# 2_main_mcu.net
KiCad netlist of a schematic drawn in Altium Designer
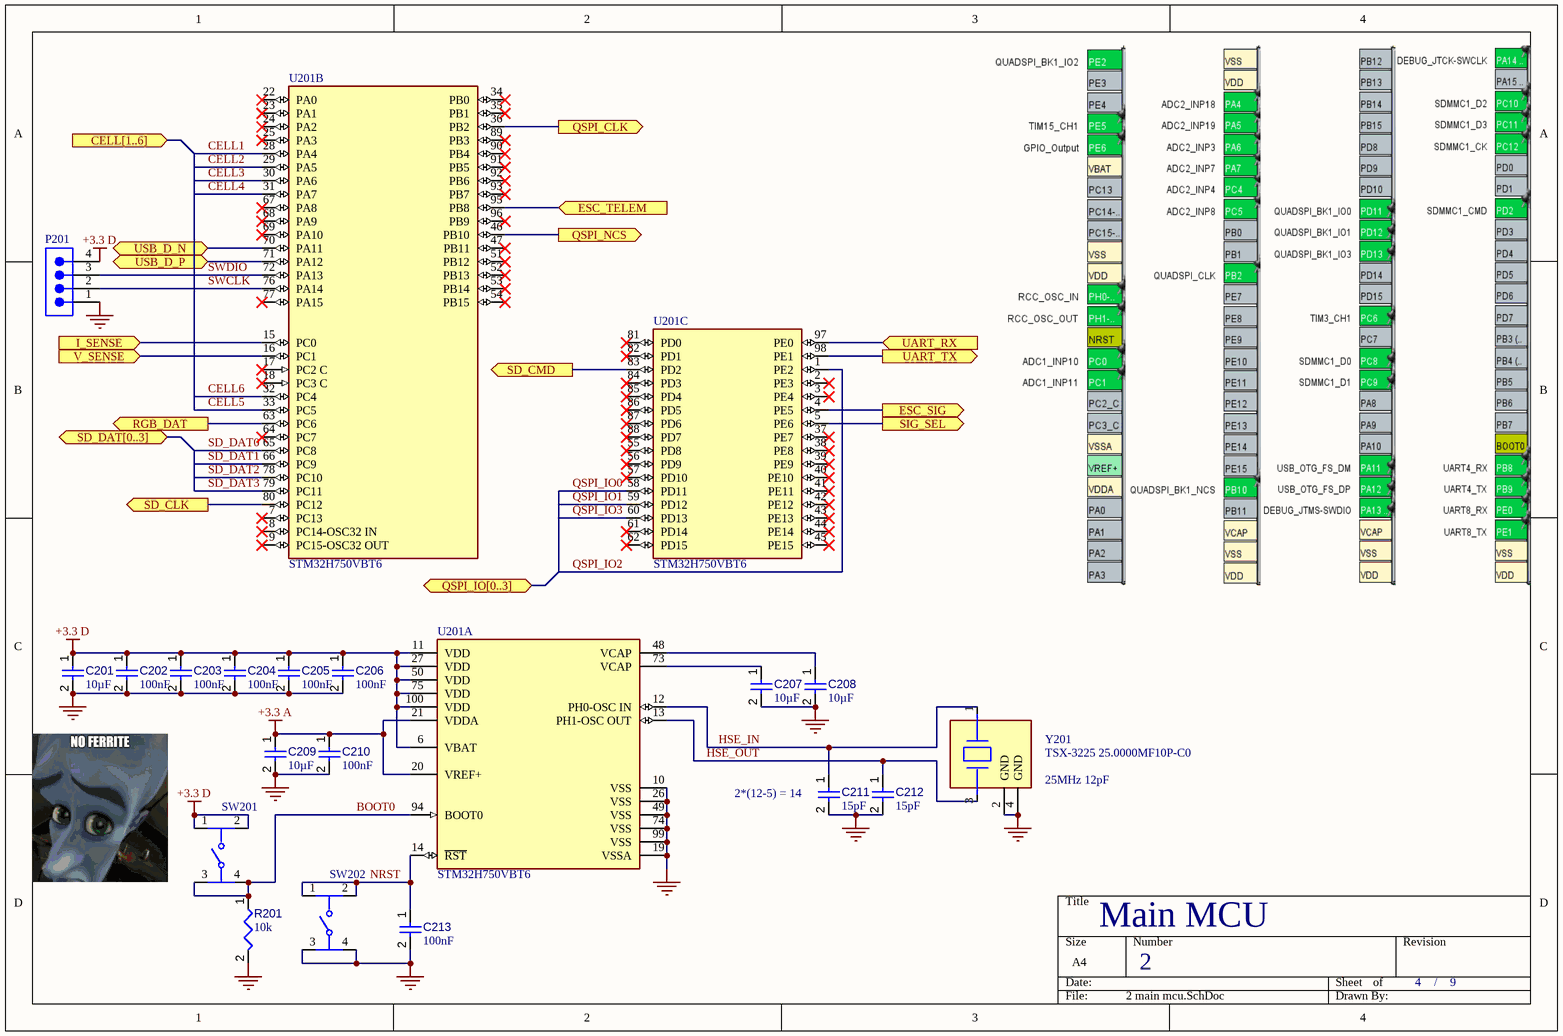
[diagram p0: 2 main mcu.SchDoc]

(export (version "E")
  (design (tool "Eeschema 10.0.6"))
  (components
    (comp (ref "C201")
      (value "10µF")
      (footprint "CAPC0603(1608)100_L")
      (description "Chip Capacitor, 10µF +/-20%, 10V, 0603, Thickness 1 mm")
      (fields (field (name "TOLERANCE") "10%") (field (name "Comment") "Capacitor 10µF +/-20% 10V 0603"))
      (libsource (lib "UBC Uncrewed Aircraft Systems") (part "CAP-NP-2"))
    )
    (comp (ref "C202")
      (value "100nF")
      (footprint "CAPC0402(1005)60_L")
      (description "Chip Capacitor, 100nF +/-20%, 25V, 0402, Thickness 0.6 mm")
      (fields (field (name "TOLERANCE") "10%") (field (name "Comment") "Capacitor 100nF +/-20% 25V 0402"))
      (libsource (lib "UBC Uncrewed Aircraft Systems") (part "CAP-NP-2"))
    )
    (comp (ref "C203")
      (value "100nF")
      (footprint "CAPC0402(1005)60_L")
      (description "Chip Capacitor, 100nF +/-20%, 25V, 0402, Thickness 0.6 mm")
      (fields (field (name "TOLERANCE") "10%") (field (name "Comment") "Capacitor 100nF +/-20% 25V 0402"))
      (libsource (lib "UBC Uncrewed Aircraft Systems") (part "CAP-NP-2"))
    )
    (comp (ref "C204")
      (value "100nF")
      (footprint "CAPC0402(1005)60_L")
      (description "Chip Capacitor, 100nF +/-20%, 25V, 0402, Thickness 0.6 mm")
      (fields (field (name "TOLERANCE") "10%") (field (name "Comment") "Capacitor 100nF +/-20% 25V 0402"))
      (libsource (lib "UBC Uncrewed Aircraft Systems") (part "CAP-NP-2"))
    )
    (comp (ref "C205")
      (value "100nF")
      (footprint "CAPC0402(1005)60_L")
      (description "Chip Capacitor, 100nF +/-20%, 25V, 0402, Thickness 0.6 mm")
      (fields (field (name "TOLERANCE") "10%") (field (name "Comment") "Capacitor 100nF +/-20% 25V 0402"))
      (libsource (lib "UBC Uncrewed Aircraft Systems") (part "CAP-NP-2"))
    )
    (comp (ref "C206")
      (value "100nF")
      (footprint "CAPC0402(1005)60_L")
      (description "Chip Capacitor, 100nF +/-20%, 25V, 0402, Thickness 0.6 mm")
      (fields (field (name "TOLERANCE") "10%") (field (name "Comment") "Capacitor 100nF +/-20% 25V 0402"))
      (libsource (lib "UBC Uncrewed Aircraft Systems") (part "CAP-NP-2"))
    )
    (comp (ref "C207")
      (value "10µF")
      (footprint "CAPC0603(1608)100_L")
      (description "Chip Capacitor, 10µF +/-20%, 10V, 0603, Thickness 1 mm")
      (fields (field (name "TOLERANCE") "10%") (field (name "Comment") "Capacitor 10µF +/-20% 10V 0603"))
      (libsource (lib "UBC Uncrewed Aircraft Systems") (part "CAP-NP-2"))
    )
    (comp (ref "C208")
      (value "10µF")
      (footprint "CAPC0603(1608)100_L")
      (description "Chip Capacitor, 10µF +/-20%, 10V, 0603, Thickness 1 mm")
      (fields (field (name "TOLERANCE") "10%") (field (name "Comment") "Capacitor 10µF +/-20% 10V 0603"))
      (libsource (lib "UBC Uncrewed Aircraft Systems") (part "CAP-NP-2"))
    )
    (comp (ref "C209")
      (value "10µF")
      (footprint "CAPC0603(1608)100_L")
      (description "Chip Capacitor, 10µF +/-20%, 10V, 0603, Thickness 1 mm")
      (fields (field (name "TOLERANCE") "10%") (field (name "Comment") "Capacitor 10µF +/-20% 10V 0603"))
      (libsource (lib "UBC Uncrewed Aircraft Systems") (part "CAP-NP-2"))
    )
    (comp (ref "C210")
      (value "100nF")
      (footprint "CAPC0402(1005)60_L")
      (description "Chip Capacitor, 100nF +/-20%, 25V, 0402, Thickness 0.6 mm")
      (fields (field (name "TOLERANCE") "10%") (field (name "Comment") "Capacitor 100nF +/-20% 25V 0402"))
      (libsource (lib "UBC Uncrewed Aircraft Systems") (part "CAP-NP-2"))
    )
    (comp (ref "C211")
      (value "15pF")
      (footprint "CAPC0402(1005)60_L")
      (description "Chip Capacitor, 15pF +/-20%, 50V, 0402, Thickness 0.6 mm")
      (fields (field (name "TOLERANCE") "5%") (field (name "JLCPCB PART #") "C1548"))
      (libsource (lib "UBC Uncrewed Aircraft Systems") (part "CAP-NP-2"))
    )
    (comp (ref "C212")
      (value "15pF")
      (footprint "CAPC0402(1005)60_L")
      (description "Chip Capacitor, 15pF +/-20%, 50V, 0402, Thickness 0.6 mm")
      (fields (field (name "TOLERANCE") "5%") (field (name "JLCPCB PART #") "C1548"))
      (libsource (lib "UBC Uncrewed Aircraft Systems") (part "CAP-NP-2"))
    )
    (comp (ref "C213")
      (value "100nF")
      (footprint "CAPC0402(1005)60_L")
      (description "Chip Capacitor, 100nF +/-20%, 25V, 0402, Thickness 0.6 mm")
      (fields (field (name "TOLERANCE") "10%") (field (name "Comment") "Capacitor 100nF +/-20% 25V 0402"))
      (libsource (lib "UBC Uncrewed Aircraft Systems") (part "CAP-NP-2"))
    )
    (comp (ref "P201")
      (value "61300411121")
      (footprint "61300411121")
      (libsource (lib "Altium Content Vault") (part "Header_Male_1R_04P"))
    )
    (comp (ref "R201")
      (value "10k")
      (footprint "RESC0402(1005)_L")
      (description "Chip Resistor, 10 kOhms, +/-1 %, 63 mW, -55 to 125 degC, 0402")
      (fields (field (name "POWER") "63mW") (field (name "TOLERANCE") "1%"))
      (libsource (lib "UBC Uncrewed Aircraft Systems") (part "RES-2"))
    )
    (comp (ref "SW201")
      (value "PTS810SJM250SMTRLFS")
      (footprint "FP-PTS810SJM250SMTRLFS-MFG")
      (description "SWITCH TACTILE SPST-NO 0.05A 16V")
      (libsource (lib "Altium Content Vault") (part "1adf0dd01260c80cf25a44bfd6b99ba"))
    )
    (comp (ref "SW202")
      (value "PTS810SJM250SMTRLFS")
      (footprint "FP-PTS810SJM250SMTRLFS-MFG")
      (description "SWITCH TACTILE SPST-NO 0.05A 16V")
      (libsource (lib "Altium Content Vault") (part "1adf0dd01260c80cf25a44bfd6b99ba"))
    )
    (comp (ref "U201")
      (value "STM32H750VBT6")
      (footprint "FP-LQFP100-1L-MFG")
      (description "IC MCU 32BIT 128KB FLASH 100LQFP")
      (fields
        (field (name "OCTOPART") "https://octopart.com/stm32h750vbt6-stmicroelectronics-94048547")
        (field (name "MANUFACTURER") "STMicroelectronics")
      )
      (libsource (lib "Altium Content Vault") (part "aca449acb2b80670ba40d015d68dc7a"))
    )
    (comp (ref "Y201")
      (value "TSX-3225 25.0000MF10P-C0")
      (footprint "FP-TSX-3225-MFG")
      (description "CRYSTAL 25.0000MHZ 18PF SMD")
      (libsource (lib "Altium Content Vault") (part "927a1cf76fcef45674bd853ccf050d4"))
    )
  )
  (nets
    (net (code "1") (name "+3.3 A") (class "Default")
      (node (ref "C209") (pin "1") (pinfunction "1_1") (pintype "passive"))
      (node (ref "C210") (pin "1") (pinfunction "1_1") (pintype "passive"))
      (node (ref "U201") (pin "20") (pinfunction "VREF+_20") (pintype "power_in"))
      (node (ref "U201") (pin "21") (pinfunction "VDDA_21") (pintype "power_in"))
    )
    (net (code "2") (name "+3.3 D") (class "Default")
      (node (ref "C201") (pin "1") (pinfunction "1_1") (pintype "passive"))
      (node (ref "C202") (pin "1") (pinfunction "1_1") (pintype "passive"))
      (node (ref "C203") (pin "1") (pinfunction "1_1") (pintype "passive"))
      (node (ref "C204") (pin "1") (pinfunction "1_1") (pintype "passive"))
      (node (ref "C205") (pin "1") (pinfunction "1_1") (pintype "passive"))
      (node (ref "C206") (pin "1") (pinfunction "1_1") (pintype "passive"))
      (node (ref "P201") (pin "4") (pinfunction "4_4") (pintype "passive"))
      (node (ref "SW201") (pin "1") (pinfunction "1_1") (pintype "passive"))
      (node (ref "SW201") (pin "2") (pinfunction "2_2") (pintype "passive"))
      (node (ref "U201") (pin "100") (pinfunction "VDD_100") (pintype "power_in"))
      (node (ref "U201") (pin "11") (pinfunction "VDD_11") (pintype "power_in"))
      (node (ref "U201") (pin "27") (pinfunction "VDD_27") (pintype "power_in"))
      (node (ref "U201") (pin "50") (pinfunction "VDD_50") (pintype "power_in"))
      (node (ref "U201") (pin "6") (pinfunction "VBAT_6") (pintype "power_in"))
      (node (ref "U201") (pin "75") (pinfunction "VDD_75") (pintype "power_in"))
    )
    (net (code "3") (name "/BOOT0") (class "Default")
      (node (ref "R201") (pin "1") (pinfunction "1_1") (pintype "passive"))
      (node (ref "SW201") (pin "3") (pinfunction "3_3") (pintype "passive"))
      (node (ref "SW201") (pin "4") (pinfunction "4_4") (pintype "passive"))
      (node (ref "U201") (pin "94") (pinfunction "BOOT0_94") (pintype "input"))
    )
    (net (code "4") (name "/CELL1") (class "Default")
      (node (ref "U201") (pin "28") (pinfunction "PA4_28") (pintype "bidirectional"))
    )
    (net (code "5") (name "/CELL2") (class "Default")
      (node (ref "U201") (pin "29") (pinfunction "PA5_29") (pintype "bidirectional"))
    )
    (net (code "6") (name "/CELL3") (class "Default")
      (node (ref "U201") (pin "30") (pinfunction "PA6_30") (pintype "bidirectional"))
    )
    (net (code "7") (name "/CELL4") (class "Default")
      (node (ref "U201") (pin "31") (pinfunction "PA7_31") (pintype "bidirectional"))
    )
    (net (code "8") (name "/CELL5") (class "Default")
      (node (ref "U201") (pin "33") (pinfunction "PC5_33") (pintype "bidirectional"))
    )
    (net (code "9") (name "/CELL6") (class "Default")
      (node (ref "U201") (pin "32") (pinfunction "PC4_32") (pintype "bidirectional"))
    )
    (net (code "11") (name "/ESC_SIG") (class "Default")
      (node (ref "U201") (pin "4") (pinfunction "PE5_4") (pintype "bidirectional"))
    )
    (net (code "12") (name "/ESC_TELEM") (class "Default")
      (node (ref "U201") (pin "95") (pinfunction "PB8_95") (pintype "bidirectional"))
    )
    (net (code "13") (name "/HSE_IN") (class "Default")
      (node (ref "C211") (pin "1") (pinfunction "1_1") (pintype "passive"))
      (node (ref "U201") (pin "12") (pinfunction "PH0-OSC_IN_12") (pintype "bidirectional"))
      (node (ref "Y201") (pin "1") (pinfunction "1_1") (pintype "passive"))
    )
    (net (code "14") (name "/HSE_OUT") (class "Default")
      (node (ref "C212") (pin "1") (pinfunction "1_1") (pintype "passive"))
      (node (ref "U201") (pin "13") (pinfunction "PH1-OSC_OUT_13") (pintype "bidirectional"))
      (node (ref "Y201") (pin "3") (pinfunction "3_3") (pintype "passive"))
    )
    (net (code "15") (name "/I_SENSE") (class "Default")
      (node (ref "U201") (pin "15") (pinfunction "PC0_15") (pintype "bidirectional"))
    )
    (net (code "16") (name "/NRST") (class "Default")
      (node (ref "C213") (pin "1") (pinfunction "1_1") (pintype "passive"))
      (node (ref "SW202") (pin "1") (pinfunction "1_1") (pintype "passive"))
      (node (ref "SW202") (pin "2") (pinfunction "2_2") (pintype "passive"))
      (node (ref "U201") (pin "14") (pinfunction "~{RST}_14") (pintype "bidirectional"))
    )
    (net (code "17") (name "/QSPI_CLK") (class "Default")
      (node (ref "U201") (pin "36") (pinfunction "PB2_36") (pintype "bidirectional"))
    )
    (net (code "18") (name "/QSPI_IO0") (class "Default")
      (node (ref "U201") (pin "58") (pinfunction "PD11_58") (pintype "bidirectional"))
    )
    (net (code "19") (name "/QSPI_IO1") (class "Default")
      (node (ref "U201") (pin "59") (pinfunction "PD12_59") (pintype "bidirectional"))
    )
    (net (code "20") (name "/QSPI_IO2") (class "Default")
      (node (ref "U201") (pin "1") (pinfunction "PE2_1") (pintype "bidirectional"))
    )
    (net (code "21") (name "/QSPI_IO3") (class "Default")
      (node (ref "U201") (pin "60") (pinfunction "PD13_60") (pintype "bidirectional"))
    )
    (net (code "23") (name "/QSPI_NCS") (class "Default")
      (node (ref "U201") (pin "46") (pinfunction "PB10_46") (pintype "bidirectional"))
    )
    (net (code "24") (name "/RGB_DAT") (class "Default")
      (node (ref "U201") (pin "63") (pinfunction "PC6_63") (pintype "bidirectional"))
    )
    (net (code "25") (name "/SD_CLK") (class "Default")
      (node (ref "U201") (pin "80") (pinfunction "PC12_80") (pintype "bidirectional"))
    )
    (net (code "26") (name "/SD_CMD") (class "Default")
      (node (ref "U201") (pin "83") (pinfunction "PD2_83") (pintype "bidirectional"))
    )
    (net (code "27") (name "/SD_DAT0") (class "Default")
      (node (ref "U201") (pin "65") (pinfunction "PC8_65") (pintype "bidirectional"))
    )
    (net (code "28") (name "/SD_DAT1") (class "Default")
      (node (ref "U201") (pin "66") (pinfunction "PC9_66") (pintype "bidirectional"))
    )
    (net (code "29") (name "/SD_DAT2") (class "Default")
      (node (ref "U201") (pin "78") (pinfunction "PC10_78") (pintype "bidirectional"))
    )
    (net (code "30") (name "/SD_DAT3") (class "Default")
      (node (ref "U201") (pin "79") (pinfunction "PC11_79") (pintype "bidirectional"))
    )
    (net (code "32") (name "/SIG_SEL") (class "Default")
      (node (ref "U201") (pin "5") (pinfunction "PE6_5") (pintype "bidirectional"))
    )
    (net (code "33") (name "/SWCLK") (class "Default")
      (node (ref "P201") (pin "2") (pinfunction "2_2") (pintype "passive"))
      (node (ref "U201") (pin "76") (pinfunction "PA14_76") (pintype "bidirectional"))
    )
    (net (code "34") (name "/SWDIO") (class "Default")
      (node (ref "P201") (pin "3") (pinfunction "3_3") (pintype "passive"))
      (node (ref "U201") (pin "72") (pinfunction "PA13_72") (pintype "bidirectional"))
    )
    (net (code "35") (name "/UART_RX") (class "Default")
      (node (ref "U201") (pin "97") (pinfunction "PE0_97") (pintype "bidirectional"))
    )
    (net (code "36") (name "/UART_TX") (class "Default")
      (node (ref "U201") (pin "98") (pinfunction "PE1_98") (pintype "bidirectional"))
    )
    (net (code "37") (name "/USB_D_N") (class "Default")
      (node (ref "U201") (pin "70") (pinfunction "PA11_70") (pintype "bidirectional"))
    )
    (net (code "38") (name "/USB_D_P") (class "Default")
      (node (ref "U201") (pin "71") (pinfunction "PA12_71") (pintype "bidirectional"))
    )
    (net (code "39") (name "/V_SENSE") (class "Default")
      (node (ref "U201") (pin "16") (pinfunction "PC1_16") (pintype "bidirectional"))
    )
    (net (code "40") (name "GND") (class "Default")
      (node (ref "C201") (pin "2") (pinfunction "2_2") (pintype "passive"))
      (node (ref "C202") (pin "2") (pinfunction "2_2") (pintype "passive"))
      (node (ref "C203") (pin "2") (pinfunction "2_2") (pintype "passive"))
      (node (ref "C204") (pin "2") (pinfunction "2_2") (pintype "passive"))
      (node (ref "C205") (pin "2") (pinfunction "2_2") (pintype "passive"))
      (node (ref "C206") (pin "2") (pinfunction "2_2") (pintype "passive"))
      (node (ref "C207") (pin "2") (pinfunction "2_2") (pintype "passive"))
      (node (ref "C208") (pin "2") (pinfunction "2_2") (pintype "passive"))
      (node (ref "C209") (pin "2") (pinfunction "2_2") (pintype "passive"))
      (node (ref "C210") (pin "2") (pinfunction "2_2") (pintype "passive"))
      (node (ref "C211") (pin "2") (pinfunction "2_2") (pintype "passive"))
      (node (ref "C212") (pin "2") (pinfunction "2_2") (pintype "passive"))
      (node (ref "C213") (pin "2") (pinfunction "2_2") (pintype "passive"))
      (node (ref "P201") (pin "1") (pinfunction "1_1") (pintype "passive"))
      (node (ref "R201") (pin "2") (pinfunction "2_2") (pintype "passive"))
      (node (ref "SW202") (pin "3") (pinfunction "3_3") (pintype "passive"))
      (node (ref "SW202") (pin "4") (pinfunction "4_4") (pintype "passive"))
      (node (ref "U201") (pin "10") (pinfunction "VSS_10") (pintype "power_in"))
      (node (ref "U201") (pin "19") (pinfunction "VSSA_19") (pintype "power_in"))
      (node (ref "U201") (pin "26") (pinfunction "VSS_26") (pintype "power_in"))
      (node (ref "U201") (pin "49") (pinfunction "VSS_49") (pintype "power_in"))
      (node (ref "U201") (pin "74") (pinfunction "VSS_74") (pintype "power_in"))
      (node (ref "U201") (pin "99") (pinfunction "VSS_99") (pintype "power_in"))
      (node (ref "Y201") (pin "2") (pinfunction "GND_2") (pintype "power_in"))
      (node (ref "Y201") (pin "4") (pinfunction "GND_4") (pintype "power_in"))
    )
    (net (code "41") (name "Net-(C207-Pad1)") (class "Default")
      (node (ref "C207") (pin "1") (pinfunction "1_1") (pintype "passive"))
      (node (ref "U201") (pin "73") (pinfunction "VCAP_73") (pintype "power_in"))
    )
    (net (code "42") (name "Net-(C208-Pad1)") (class "Default")
      (node (ref "C208") (pin "1") (pinfunction "1_1") (pintype "passive"))
      (node (ref "U201") (pin "48") (pinfunction "VCAP_48") (pintype "power_in"))
    )
    (net (code "43") (name "unconnected-(U201B-PA0-Pad22)") (class "Default")
      (node (ref "U201") (pin "22") (pinfunction "PA0_22") (pintype "bidirectional+no_connect"))
    )
    (net (code "44") (name "unconnected-(U201B-PA1-Pad23)") (class "Default")
      (node (ref "U201") (pin "23") (pinfunction "PA1_23") (pintype "bidirectional+no_connect"))
    )
    (net (code "45") (name "unconnected-(U201B-PA2-Pad24)") (class "Default")
      (node (ref "U201") (pin "24") (pinfunction "PA2_24") (pintype "bidirectional+no_connect"))
    )
    (net (code "46") (name "unconnected-(U201B-PA3-Pad25)") (class "Default")
      (node (ref "U201") (pin "25") (pinfunction "PA3_25") (pintype "bidirectional+no_connect"))
    )
    (net (code "47") (name "unconnected-(U201B-PA8-Pad67)") (class "Default")
      (node (ref "U201") (pin "67") (pinfunction "PA8_67") (pintype "bidirectional+no_connect"))
    )
    (net (code "48") (name "unconnected-(U201B-PA9-Pad68)") (class "Default")
      (node (ref "U201") (pin "68") (pinfunction "PA9_68") (pintype "bidirectional+no_connect"))
    )
    (net (code "49") (name "unconnected-(U201B-PA10-Pad69)") (class "Default")
      (node (ref "U201") (pin "69") (pinfunction "PA10_69") (pintype "bidirectional+no_connect"))
    )
    (net (code "50") (name "unconnected-(U201B-PA15-Pad77)") (class "Default")
      (node (ref "U201") (pin "77") (pinfunction "PA15_77") (pintype "bidirectional+no_connect"))
    )
    (net (code "51") (name "unconnected-(U201B-PB0-Pad34)") (class "Default")
      (node (ref "U201") (pin "34") (pinfunction "PB0_34") (pintype "bidirectional+no_connect"))
    )
    (net (code "52") (name "unconnected-(U201B-PB1-Pad35)") (class "Default")
      (node (ref "U201") (pin "35") (pinfunction "PB1_35") (pintype "bidirectional+no_connect"))
    )
    (net (code "53") (name "unconnected-(U201B-PB3-Pad89)") (class "Default")
      (node (ref "U201") (pin "89") (pinfunction "PB3_89") (pintype "bidirectional+no_connect"))
    )
    (net (code "54") (name "unconnected-(U201B-PB4-Pad90)") (class "Default")
      (node (ref "U201") (pin "90") (pinfunction "PB4_90") (pintype "bidirectional+no_connect"))
    )
    (net (code "55") (name "unconnected-(U201B-PB5-Pad91)") (class "Default")
      (node (ref "U201") (pin "91") (pinfunction "PB5_91") (pintype "bidirectional+no_connect"))
    )
    (net (code "56") (name "unconnected-(U201B-PB6-Pad92)") (class "Default")
      (node (ref "U201") (pin "92") (pinfunction "PB6_92") (pintype "bidirectional+no_connect"))
    )
    (net (code "57") (name "unconnected-(U201B-PB7-Pad93)") (class "Default")
      (node (ref "U201") (pin "93") (pinfunction "PB7_93") (pintype "bidirectional+no_connect"))
    )
    (net (code "58") (name "unconnected-(U201B-PB9-Pad96)") (class "Default")
      (node (ref "U201") (pin "96") (pinfunction "PB9_96") (pintype "bidirectional+no_connect"))
    )
    (net (code "59") (name "unconnected-(U201B-PB11-Pad47)") (class "Default")
      (node (ref "U201") (pin "47") (pinfunction "PB11_47") (pintype "bidirectional+no_connect"))
    )
    (net (code "60") (name "unconnected-(U201B-PB12-Pad51)") (class "Default")
      (node (ref "U201") (pin "51") (pinfunction "PB12_51") (pintype "bidirectional+no_connect"))
    )
    (net (code "61") (name "unconnected-(U201B-PB13-Pad52)") (class "Default")
      (node (ref "U201") (pin "52") (pinfunction "PB13_52") (pintype "bidirectional+no_connect"))
    )
    (net (code "62") (name "unconnected-(U201B-PB14-Pad53)") (class "Default")
      (node (ref "U201") (pin "53") (pinfunction "PB14_53") (pintype "bidirectional+no_connect"))
    )
    (net (code "63") (name "unconnected-(U201B-PB15-Pad54)") (class "Default")
      (node (ref "U201") (pin "54") (pinfunction "PB15_54") (pintype "bidirectional+no_connect"))
    )
    (net (code "64") (name "unconnected-(U201B-PC2_C-Pad17)") (class "Default")
      (node (ref "U201") (pin "17") (pinfunction "PC2_C_17") (pintype "input+no_connect"))
    )
    (net (code "65") (name "unconnected-(U201B-PC3_C-Pad18)") (class "Default")
      (node (ref "U201") (pin "18") (pinfunction "PC3_C_18") (pintype "input+no_connect"))
    )
    (net (code "66") (name "unconnected-(U201B-PC7-Pad64)") (class "Default")
      (node (ref "U201") (pin "64") (pinfunction "PC7_64") (pintype "bidirectional+no_connect"))
    )
    (net (code "67") (name "unconnected-(U201B-PC13-Pad7)") (class "Default")
      (node (ref "U201") (pin "7") (pinfunction "PC13_7") (pintype "bidirectional+no_connect"))
    )
    (net (code "68") (name "unconnected-(U201B-PC14-OSC32_IN-Pad8)") (class "Default")
      (node (ref "U201") (pin "8") (pinfunction "PC14-OSC32_IN_8") (pintype "bidirectional+no_connect"))
    )
    (net (code "69") (name "unconnected-(U201B-PC15-OSC32_OUT-Pad9)") (class "Default")
      (node (ref "U201") (pin "9") (pinfunction "PC15-OSC32_OUT_9") (pintype "bidirectional+no_connect"))
    )
    (net (code "70") (name "unconnected-(U201C-PD0-Pad81)") (class "Default")
      (node (ref "U201") (pin "81") (pinfunction "PD0_81") (pintype "bidirectional+no_connect"))
    )
    (net (code "71") (name "unconnected-(U201C-PD1-Pad82)") (class "Default")
      (node (ref "U201") (pin "82") (pinfunction "PD1_82") (pintype "bidirectional+no_connect"))
    )
    (net (code "72") (name "unconnected-(U201C-PD3-Pad84)") (class "Default")
      (node (ref "U201") (pin "84") (pinfunction "PD3_84") (pintype "bidirectional+no_connect"))
    )
    (net (code "73") (name "unconnected-(U201C-PD4-Pad85)") (class "Default")
      (node (ref "U201") (pin "85") (pinfunction "PD4_85") (pintype "bidirectional+no_connect"))
    )
    (net (code "74") (name "unconnected-(U201C-PD5-Pad86)") (class "Default")
      (node (ref "U201") (pin "86") (pinfunction "PD5_86") (pintype "bidirectional+no_connect"))
    )
    (net (code "75") (name "unconnected-(U201C-PD6-Pad87)") (class "Default")
      (node (ref "U201") (pin "87") (pinfunction "PD6_87") (pintype "bidirectional+no_connect"))
    )
    (net (code "76") (name "unconnected-(U201C-PD7-Pad88)") (class "Default")
      (node (ref "U201") (pin "88") (pinfunction "PD7_88") (pintype "bidirectional+no_connect"))
    )
    (net (code "77") (name "unconnected-(U201C-PD8-Pad55)") (class "Default")
      (node (ref "U201") (pin "55") (pinfunction "PD8_55") (pintype "bidirectional+no_connect"))
    )
    (net (code "78") (name "unconnected-(U201C-PD9-Pad56)") (class "Default")
      (node (ref "U201") (pin "56") (pinfunction "PD9_56") (pintype "bidirectional+no_connect"))
    )
    (net (code "79") (name "unconnected-(U201C-PD10-Pad57)") (class "Default")
      (node (ref "U201") (pin "57") (pinfunction "PD10_57") (pintype "bidirectional+no_connect"))
    )
    (net (code "80") (name "unconnected-(U201C-PD14-Pad61)") (class "Default")
      (node (ref "U201") (pin "61") (pinfunction "PD14_61") (pintype "bidirectional+no_connect"))
    )
    (net (code "81") (name "unconnected-(U201C-PD15-Pad62)") (class "Default")
      (node (ref "U201") (pin "62") (pinfunction "PD15_62") (pintype "bidirectional+no_connect"))
    )
    (net (code "82") (name "unconnected-(U201C-PE3-Pad2)") (class "Default")
      (node (ref "U201") (pin "2") (pinfunction "PE3_2") (pintype "bidirectional+no_connect"))
    )
    (net (code "83") (name "unconnected-(U201C-PE4-Pad3)") (class "Default")
      (node (ref "U201") (pin "3") (pinfunction "PE4_3") (pintype "bidirectional+no_connect"))
    )
    (net (code "84") (name "unconnected-(U201C-PE7-Pad37)") (class "Default")
      (node (ref "U201") (pin "37") (pinfunction "PE7_37") (pintype "bidirectional+no_connect"))
    )
    (net (code "85") (name "unconnected-(U201C-PE8-Pad38)") (class "Default")
      (node (ref "U201") (pin "38") (pinfunction "PE8_38") (pintype "bidirectional+no_connect"))
    )
    (net (code "86") (name "unconnected-(U201C-PE9-Pad39)") (class "Default")
      (node (ref "U201") (pin "39") (pinfunction "PE9_39") (pintype "bidirectional+no_connect"))
    )
    (net (code "87") (name "unconnected-(U201C-PE10-Pad40)") (class "Default")
      (node (ref "U201") (pin "40") (pinfunction "PE10_40") (pintype "bidirectional+no_connect"))
    )
    (net (code "88") (name "unconnected-(U201C-PE11-Pad41)") (class "Default")
      (node (ref "U201") (pin "41") (pinfunction "PE11_41") (pintype "bidirectional+no_connect"))
    )
    (net (code "89") (name "unconnected-(U201C-PE12-Pad42)") (class "Default")
      (node (ref "U201") (pin "42") (pinfunction "PE12_42") (pintype "bidirectional+no_connect"))
    )
    (net (code "90") (name "unconnected-(U201C-PE13-Pad43)") (class "Default")
      (node (ref "U201") (pin "43") (pinfunction "PE13_43") (pintype "bidirectional+no_connect"))
    )
    (net (code "91") (name "unconnected-(U201C-PE14-Pad44)") (class "Default")
      (node (ref "U201") (pin "44") (pinfunction "PE14_44") (pintype "bidirectional+no_connect"))
    )
    (net (code "92") (name "unconnected-(U201C-PE15-Pad45)") (class "Default")
      (node (ref "U201") (pin "45") (pinfunction "PE15_45") (pintype "bidirectional+no_connect"))
    )
  )
)
